# timing.net
KiCad netlist of a schematic drawn in Altium Designer
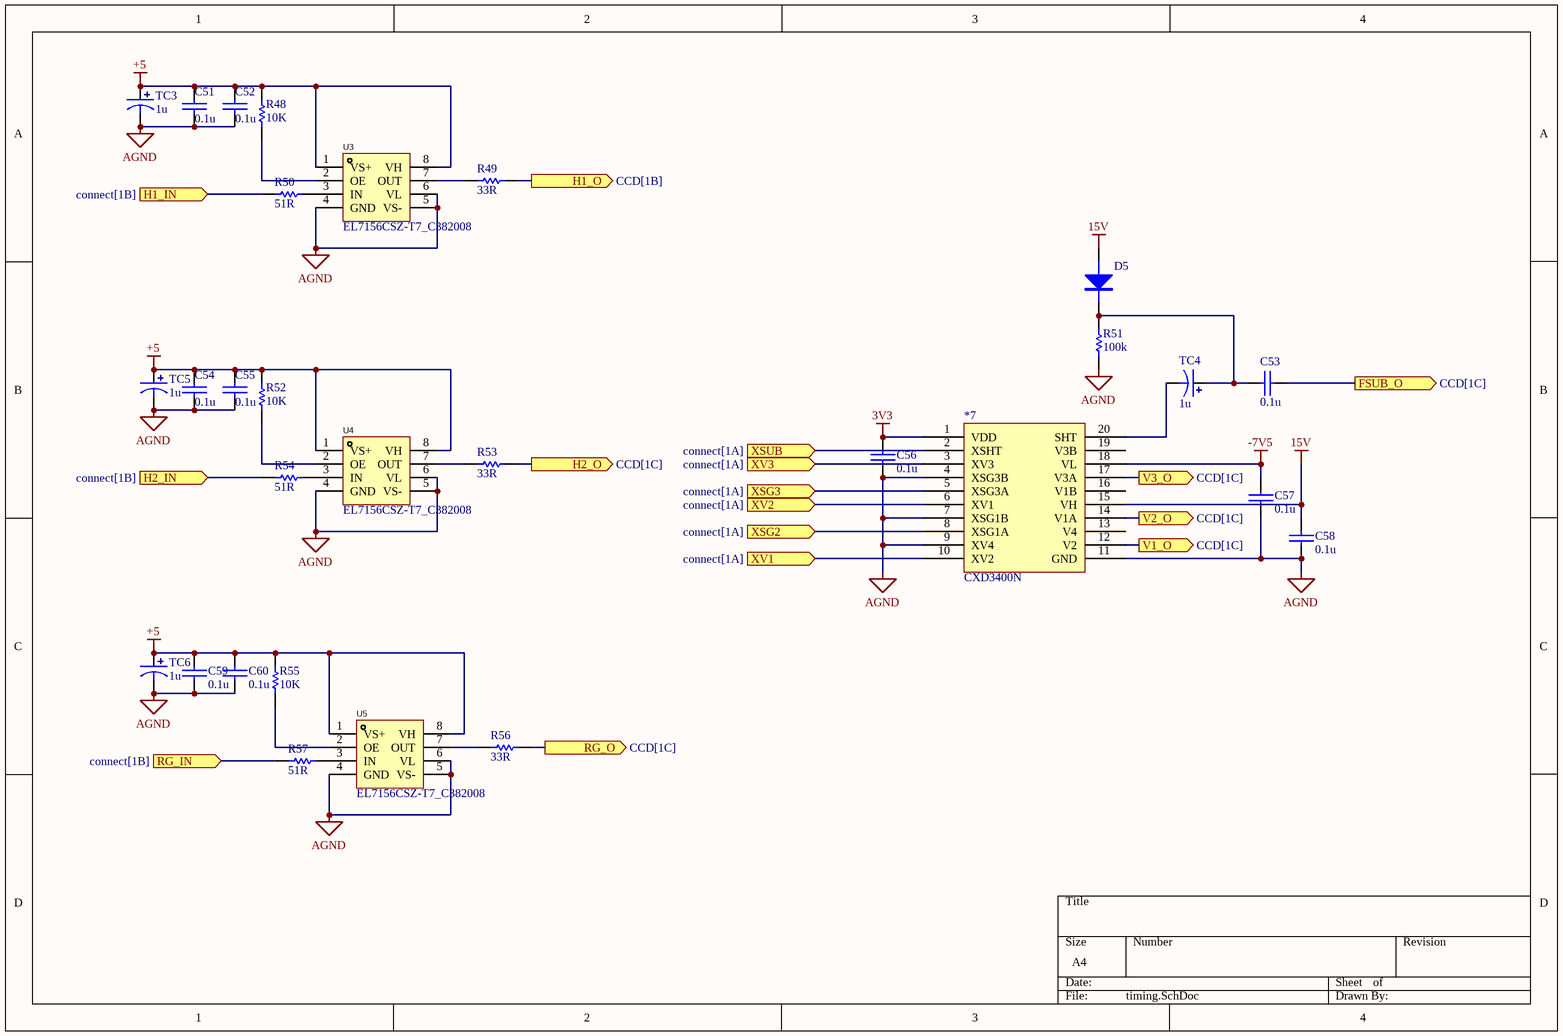
[diagram p0: timing.SchDoc]

(export (version "E")
  (design (tool "Eeschema 10.0.6"))
  (components
    (comp (ref "*7")
      (value "CXD3400N")
      (footprint "CXD3400N")
      (description "6通道垂直时钟驱动器")
      (libsource (lib "0.05-mylib") (part "CXD3400N"))
    )
    (comp (ref "C51")
      (value "0.1u")
      (footprint "0603C")
      (description "无极性电容")
      (libsource (lib "1.00-阻容感") (part "CAP"))
    )
    (comp (ref "C52")
      (value "0.1u")
      (footprint "0603C")
      (description "无极性电容")
      (libsource (lib "1.00-阻容感") (part "CAP"))
    )
    (comp (ref "C53")
      (value "0.1u")
      (footprint "0603C")
      (description "无极性电容")
      (libsource (lib "1.00-阻容感") (part "CAP"))
    )
    (comp (ref "C54")
      (value "0.1u")
      (footprint "0603C")
      (description "无极性电容")
      (libsource (lib "1.00-阻容感") (part "CAP"))
    )
    (comp (ref "C55")
      (value "0.1u")
      (footprint "0603C")
      (description "无极性电容")
      (libsource (lib "1.00-阻容感") (part "CAP"))
    )
    (comp (ref "C56")
      (value "0.1u")
      (footprint "0603C")
      (description "无极性电容")
      (libsource (lib "1.00-阻容感") (part "CAP"))
    )
    (comp (ref "C57")
      (value "0.1u")
      (footprint "0603C")
      (description "无极性电容")
      (libsource (lib "1.00-阻容感") (part "CAP"))
    )
    (comp (ref "C58")
      (value "0.1u")
      (footprint "0603C")
      (description "无极性电容")
      (libsource (lib "1.00-阻容感") (part "CAP"))
    )
    (comp (ref "C59")
      (value "0.1u")
      (footprint "0603C")
      (description "无极性电容")
      (libsource (lib "1.00-阻容感") (part "CAP"))
    )
    (comp (ref "C60")
      (value "0.1u")
      (footprint "0603C")
      (description "无极性电容")
      (libsource (lib "1.00-阻容感") (part "CAP"))
    )
    (comp (ref "D5")
      (value "DIODE")
      (footprint "SMA/DO-214AC")
      (description "普通二极管")
      (libsource (lib "2.00-二极管") (part "DIODE"))
    )
    (comp (ref "R48")
      (value "10K")
      (footprint "0603R")
      (description "电阻")
      (libsource (lib "1.00-阻容感") (part "RES"))
    )
    (comp (ref "R49")
      (value "33R")
      (footprint "0603R")
      (description "电阻")
      (libsource (lib "1.00-阻容感") (part "RES"))
    )
    (comp (ref "R50")
      (value "51R")
      (footprint "0603R")
      (description "电阻")
      (libsource (lib "1.00-阻容感") (part "RES"))
    )
    (comp (ref "R51")
      (value "100k")
      (footprint "0603R")
      (description "电阻")
      (libsource (lib "1.00-阻容感") (part "RES"))
    )
    (comp (ref "R52")
      (value "10K")
      (footprint "0603R")
      (description "电阻")
      (libsource (lib "1.00-阻容感") (part "RES"))
    )
    (comp (ref "R53")
      (value "33R")
      (footprint "0603R")
      (description "电阻")
      (libsource (lib "1.00-阻容感") (part "RES"))
    )
    (comp (ref "R54")
      (value "51R")
      (footprint "0603R")
      (description "电阻")
      (libsource (lib "1.00-阻容感") (part "RES"))
    )
    (comp (ref "R55")
      (value "10K")
      (footprint "0603R")
      (description "电阻")
      (libsource (lib "1.00-阻容感") (part "RES"))
    )
    (comp (ref "R56")
      (value "33R")
      (footprint "0603R")
      (description "电阻")
      (libsource (lib "1.00-阻容感") (part "RES"))
    )
    (comp (ref "R57")
      (value "51R")
      (footprint "0603R")
      (description "电阻")
      (libsource (lib "1.00-阻容感") (part "RES"))
    )
    (comp (ref "TC3")
      (value "1u")
      (footprint "TAJ-A/3216")
      (description "钽电容")
      (libsource (lib "1.00-阻容感") (part "TCAP"))
    )
    (comp (ref "TC4")
      (value "1u")
      (footprint "TAJ-A/3216")
      (description "钽电容")
      (libsource (lib "1.00-阻容感") (part "TCAP"))
    )
    (comp (ref "TC5")
      (value "1u")
      (footprint "TAJ-A/3216")
      (description "钽电容")
      (libsource (lib "1.00-阻容感") (part "TCAP"))
    )
    (comp (ref "TC6")
      (value "1u")
      (footprint "TAJ-A/3216")
      (description "钽电容")
      (libsource (lib "1.00-阻容感") (part "TCAP"))
    )
    (comp (ref "U3")
      (value "EL7156CSZ-T7_C382008")
      (footprint "SOIC-8")
      (description "栅极驱动器")
      (fields
        (field (name "MANUFACTURER") "Intersil(英特矽尔)")
        (field (name "MANUFACTURER PART") "EL7156CSZ-T7")
      )
      (libsource (lib "0.05-mylib") (part "EL7156CSZ-T7"))
    )
    (comp (ref "U4")
      (value "EL7156CSZ-T7_C382008")
      (footprint "SOIC-8")
      (description "栅极驱动器")
      (fields
        (field (name "MANUFACTURER") "Intersil(英特矽尔)")
        (field (name "MANUFACTURER PART") "EL7156CSZ-T7")
      )
      (libsource (lib "0.05-mylib") (part "EL7156CSZ-T7"))
    )
    (comp (ref "U5")
      (value "EL7156CSZ-T7_C382008")
      (footprint "SOIC-8")
      (description "栅极驱动器")
      (fields
        (field (name "MANUFACTURER") "Intersil(英特矽尔)")
        (field (name "MANUFACTURER PART") "EL7156CSZ-T7")
      )
      (libsource (lib "0.05-mylib") (part "EL7156CSZ-T7"))
    )
  )
  (nets
    (net (code "1") (name "+5") (class "Default")
      (node (ref "C51") (pin "1") (pinfunction "1_1") (pintype "passive"))
      (node (ref "C52") (pin "1") (pinfunction "1_1") (pintype "passive"))
      (node (ref "C54") (pin "1") (pinfunction "1_1") (pintype "passive"))
      (node (ref "C55") (pin "1") (pinfunction "1_1") (pintype "passive"))
      (node (ref "C59") (pin "1") (pinfunction "1_1") (pintype "passive"))
      (node (ref "C60") (pin "1") (pinfunction "1_1") (pintype "passive"))
      (node (ref "R48") (pin "1") (pinfunction "1_1") (pintype "passive"))
      (node (ref "R52") (pin "1") (pinfunction "1_1") (pintype "passive"))
      (node (ref "R55") (pin "1") (pinfunction "1_1") (pintype "passive"))
      (node (ref "TC3") (pin "1") (pinfunction "1_1") (pintype "passive"))
      (node (ref "TC5") (pin "1") (pinfunction "1_1") (pintype "passive"))
      (node (ref "TC6") (pin "1") (pinfunction "1_1") (pintype "passive"))
      (node (ref "U3") (pin "1") (pinfunction "VS+_1") (pintype "passive"))
      (node (ref "U3") (pin "8") (pinfunction "VH_8") (pintype "passive"))
      (node (ref "U4") (pin "1") (pinfunction "VS+_1") (pintype "passive"))
      (node (ref "U4") (pin "8") (pinfunction "VH_8") (pintype "passive"))
      (node (ref "U5") (pin "1") (pinfunction "VS+_1") (pintype "passive"))
      (node (ref "U5") (pin "8") (pinfunction "VH_8") (pintype "passive"))
    )
    (net (code "2") (name "-7V5") (class "Default")
      (node (ref "*7") (pin "18") (pinfunction "VL_18") (pintype "passive"))
      (node (ref "C57") (pin "2") (pinfunction "2_2") (pintype "passive"))
    )
    (net (code "3") (name "/FSUB_O") (class "Default")
      (node (ref "C53") (pin "1") (pinfunction "1_1") (pintype "passive"))
    )
    (net (code "4") (name "/H1_IN") (class "Default")
      (node (ref "R50") (pin "2") (pinfunction "2_2") (pintype "passive"))
    )
    (net (code "5") (name "/H1_O") (class "Default")
      (node (ref "R49") (pin "1") (pinfunction "1_1") (pintype "passive"))
    )
    (net (code "6") (name "/H2_IN") (class "Default")
      (node (ref "R54") (pin "2") (pinfunction "2_2") (pintype "passive"))
    )
    (net (code "7") (name "/H2_O") (class "Default")
      (node (ref "R53") (pin "1") (pinfunction "1_1") (pintype "passive"))
    )
    (net (code "8") (name "/RG_IN") (class "Default")
      (node (ref "R57") (pin "2") (pinfunction "2_2") (pintype "passive"))
    )
    (net (code "9") (name "/RG_O") (class "Default")
      (node (ref "R56") (pin "1") (pinfunction "1_1") (pintype "passive"))
    )
    (net (code "10") (name "/V1_O") (class "Default")
      (node (ref "*7") (pin "12") (pinfunction "V2_12") (pintype "passive"))
    )
    (net (code "11") (name "/V2_O") (class "Default")
      (node (ref "*7") (pin "14") (pinfunction "V1A_14") (pintype "passive"))
    )
    (net (code "12") (name "/V3_O") (class "Default")
      (node (ref "*7") (pin "17") (pinfunction "V3A_17") (pintype "passive"))
    )
    (net (code "13") (name "/XSG2") (class "Default")
      (node (ref "*7") (pin "8") (pinfunction "XSG1A_8") (pintype "passive"))
    )
    (net (code "14") (name "/XSG3") (class "Default")
      (node (ref "*7") (pin "5") (pinfunction "XSG3A_5") (pintype "passive"))
    )
    (net (code "15") (name "/XSUB") (class "Default")
      (node (ref "*7") (pin "2") (pinfunction "XSHT_2") (pintype "passive"))
    )
    (net (code "16") (name "/XV1") (class "Default")
      (node (ref "*7") (pin "10") (pinfunction "XV2_10") (pintype "passive"))
    )
    (net (code "17") (name "/XV2") (class "Default")
      (node (ref "*7") (pin "6") (pinfunction "XV1_6") (pintype "passive"))
    )
    (net (code "18") (name "/XV3") (class "Default")
      (node (ref "*7") (pin "3") (pinfunction "XV3_3") (pintype "passive"))
    )
    (net (code "19") (name "3V3") (class "Default")
      (node (ref "*7") (pin "1") (pinfunction "VDD_1") (pintype "passive"))
      (node (ref "C56") (pin "2") (pinfunction "2_2") (pintype "passive"))
    )
    (net (code "20") (name "15V") (class "Default")
      (node (ref "*7") (pin "15") (pinfunction "VH_15") (pintype "passive"))
      (node (ref "C58") (pin "2") (pinfunction "2_2") (pintype "passive"))
      (node (ref "D5") (pin "A") (pinfunction "A_A") (pintype "passive"))
    )
    (net (code "21") (name "AGND") (class "Default")
      (node (ref "*7") (pin "11") (pinfunction "GND_11") (pintype "passive"))
      (node (ref "*7") (pin "4") (pinfunction "XSG3B_4") (pintype "passive"))
      (node (ref "*7") (pin "7") (pinfunction "XSG1B_7") (pintype "passive"))
      (node (ref "*7") (pin "9") (pinfunction "XV4_9") (pintype "passive"))
      (node (ref "C51") (pin "2") (pinfunction "2_2") (pintype "passive"))
      (node (ref "C52") (pin "2") (pinfunction "2_2") (pintype "passive"))
      (node (ref "C54") (pin "2") (pinfunction "2_2") (pintype "passive"))
      (node (ref "C55") (pin "2") (pinfunction "2_2") (pintype "passive"))
      (node (ref "C56") (pin "1") (pinfunction "1_1") (pintype "passive"))
      (node (ref "C57") (pin "1") (pinfunction "1_1") (pintype "passive"))
      (node (ref "C58") (pin "1") (pinfunction "1_1") (pintype "passive"))
      (node (ref "C59") (pin "2") (pinfunction "2_2") (pintype "passive"))
      (node (ref "C60") (pin "2") (pinfunction "2_2") (pintype "passive"))
      (node (ref "R51") (pin "1") (pinfunction "1_1") (pintype "passive"))
      (node (ref "TC3") (pin "2") (pinfunction "2_2") (pintype "passive"))
      (node (ref "TC5") (pin "2") (pinfunction "2_2") (pintype "passive"))
      (node (ref "TC6") (pin "2") (pinfunction "2_2") (pintype "passive"))
      (node (ref "U3") (pin "4") (pinfunction "GND_4") (pintype "passive"))
      (node (ref "U3") (pin "5") (pinfunction "VS-_5") (pintype "passive"))
      (node (ref "U3") (pin "6") (pinfunction "VL_6") (pintype "passive"))
      (node (ref "U4") (pin "4") (pinfunction "GND_4") (pintype "passive"))
      (node (ref "U4") (pin "5") (pinfunction "VS-_5") (pintype "passive"))
      (node (ref "U4") (pin "6") (pinfunction "VL_6") (pintype "passive"))
      (node (ref "U5") (pin "4") (pinfunction "GND_4") (pintype "passive"))
      (node (ref "U5") (pin "5") (pinfunction "VS-_5") (pintype "passive"))
      (node (ref "U5") (pin "6") (pinfunction "VL_6") (pintype "passive"))
    )
    (net (code "22") (name "Net-(*7-SHT)") (class "Default")
      (node (ref "*7") (pin "20") (pinfunction "SHT_20") (pintype "passive"))
      (node (ref "TC4") (pin "2") (pinfunction "2_2") (pintype "passive"))
    )
    (net (code "23") (name "Net-(C53-Pad2)") (class "Default")
      (node (ref "C53") (pin "2") (pinfunction "2_2") (pintype "passive"))
      (node (ref "D5") (pin "K") (pinfunction "K_K") (pintype "passive"))
      (node (ref "R51") (pin "2") (pinfunction "2_2") (pintype "passive"))
      (node (ref "TC4") (pin "1") (pinfunction "1_1") (pintype "passive"))
    )
    (net (code "24") (name "Net-(U3-IN)") (class "Default")
      (node (ref "R50") (pin "1") (pinfunction "1_1") (pintype "passive"))
      (node (ref "U3") (pin "3") (pinfunction "IN_3") (pintype "passive"))
    )
    (net (code "25") (name "Net-(U3-OE)") (class "Default")
      (node (ref "R48") (pin "2") (pinfunction "2_2") (pintype "passive"))
      (node (ref "U3") (pin "2") (pinfunction "OE_2") (pintype "passive"))
    )
    (net (code "26") (name "Net-(U3-OUT)") (class "Default")
      (node (ref "R49") (pin "2") (pinfunction "2_2") (pintype "passive"))
      (node (ref "U3") (pin "7") (pinfunction "OUT_7") (pintype "passive"))
    )
    (net (code "27") (name "Net-(U4-IN)") (class "Default")
      (node (ref "R54") (pin "1") (pinfunction "1_1") (pintype "passive"))
      (node (ref "U4") (pin "3") (pinfunction "IN_3") (pintype "passive"))
    )
    (net (code "28") (name "Net-(U4-OE)") (class "Default")
      (node (ref "R52") (pin "2") (pinfunction "2_2") (pintype "passive"))
      (node (ref "U4") (pin "2") (pinfunction "OE_2") (pintype "passive"))
    )
    (net (code "29") (name "Net-(U4-OUT)") (class "Default")
      (node (ref "R53") (pin "2") (pinfunction "2_2") (pintype "passive"))
      (node (ref "U4") (pin "7") (pinfunction "OUT_7") (pintype "passive"))
    )
    (net (code "30") (name "Net-(U5-IN)") (class "Default")
      (node (ref "R57") (pin "1") (pinfunction "1_1") (pintype "passive"))
      (node (ref "U5") (pin "3") (pinfunction "IN_3") (pintype "passive"))
    )
    (net (code "31") (name "Net-(U5-OE)") (class "Default")
      (node (ref "R55") (pin "2") (pinfunction "2_2") (pintype "passive"))
      (node (ref "U5") (pin "2") (pinfunction "OE_2") (pintype "passive"))
    )
    (net (code "32") (name "Net-(U5-OUT)") (class "Default")
      (node (ref "R56") (pin "2") (pinfunction "2_2") (pintype "passive"))
      (node (ref "U5") (pin "7") (pinfunction "OUT_7") (pintype "passive"))
    )
    (net (code "33") (name "unconnected-(*7-V1B-Pad16)") (class "Default")
      (node (ref "*7") (pin "16") (pinfunction "V1B_16") (pintype "passive"))
    )
    (net (code "34") (name "unconnected-(*7-V3B-Pad19)") (class "Default")
      (node (ref "*7") (pin "19") (pinfunction "V3B_19") (pintype "passive"))
    )
    (net (code "35") (name "unconnected-(*7-V4-Pad13)") (class "Default")
      (node (ref "*7") (pin "13") (pinfunction "V4_13") (pintype "passive"))
    )
  )
)
